# Modulo_control.net
KiCad netlist of a schematic drawn in Altium Designer
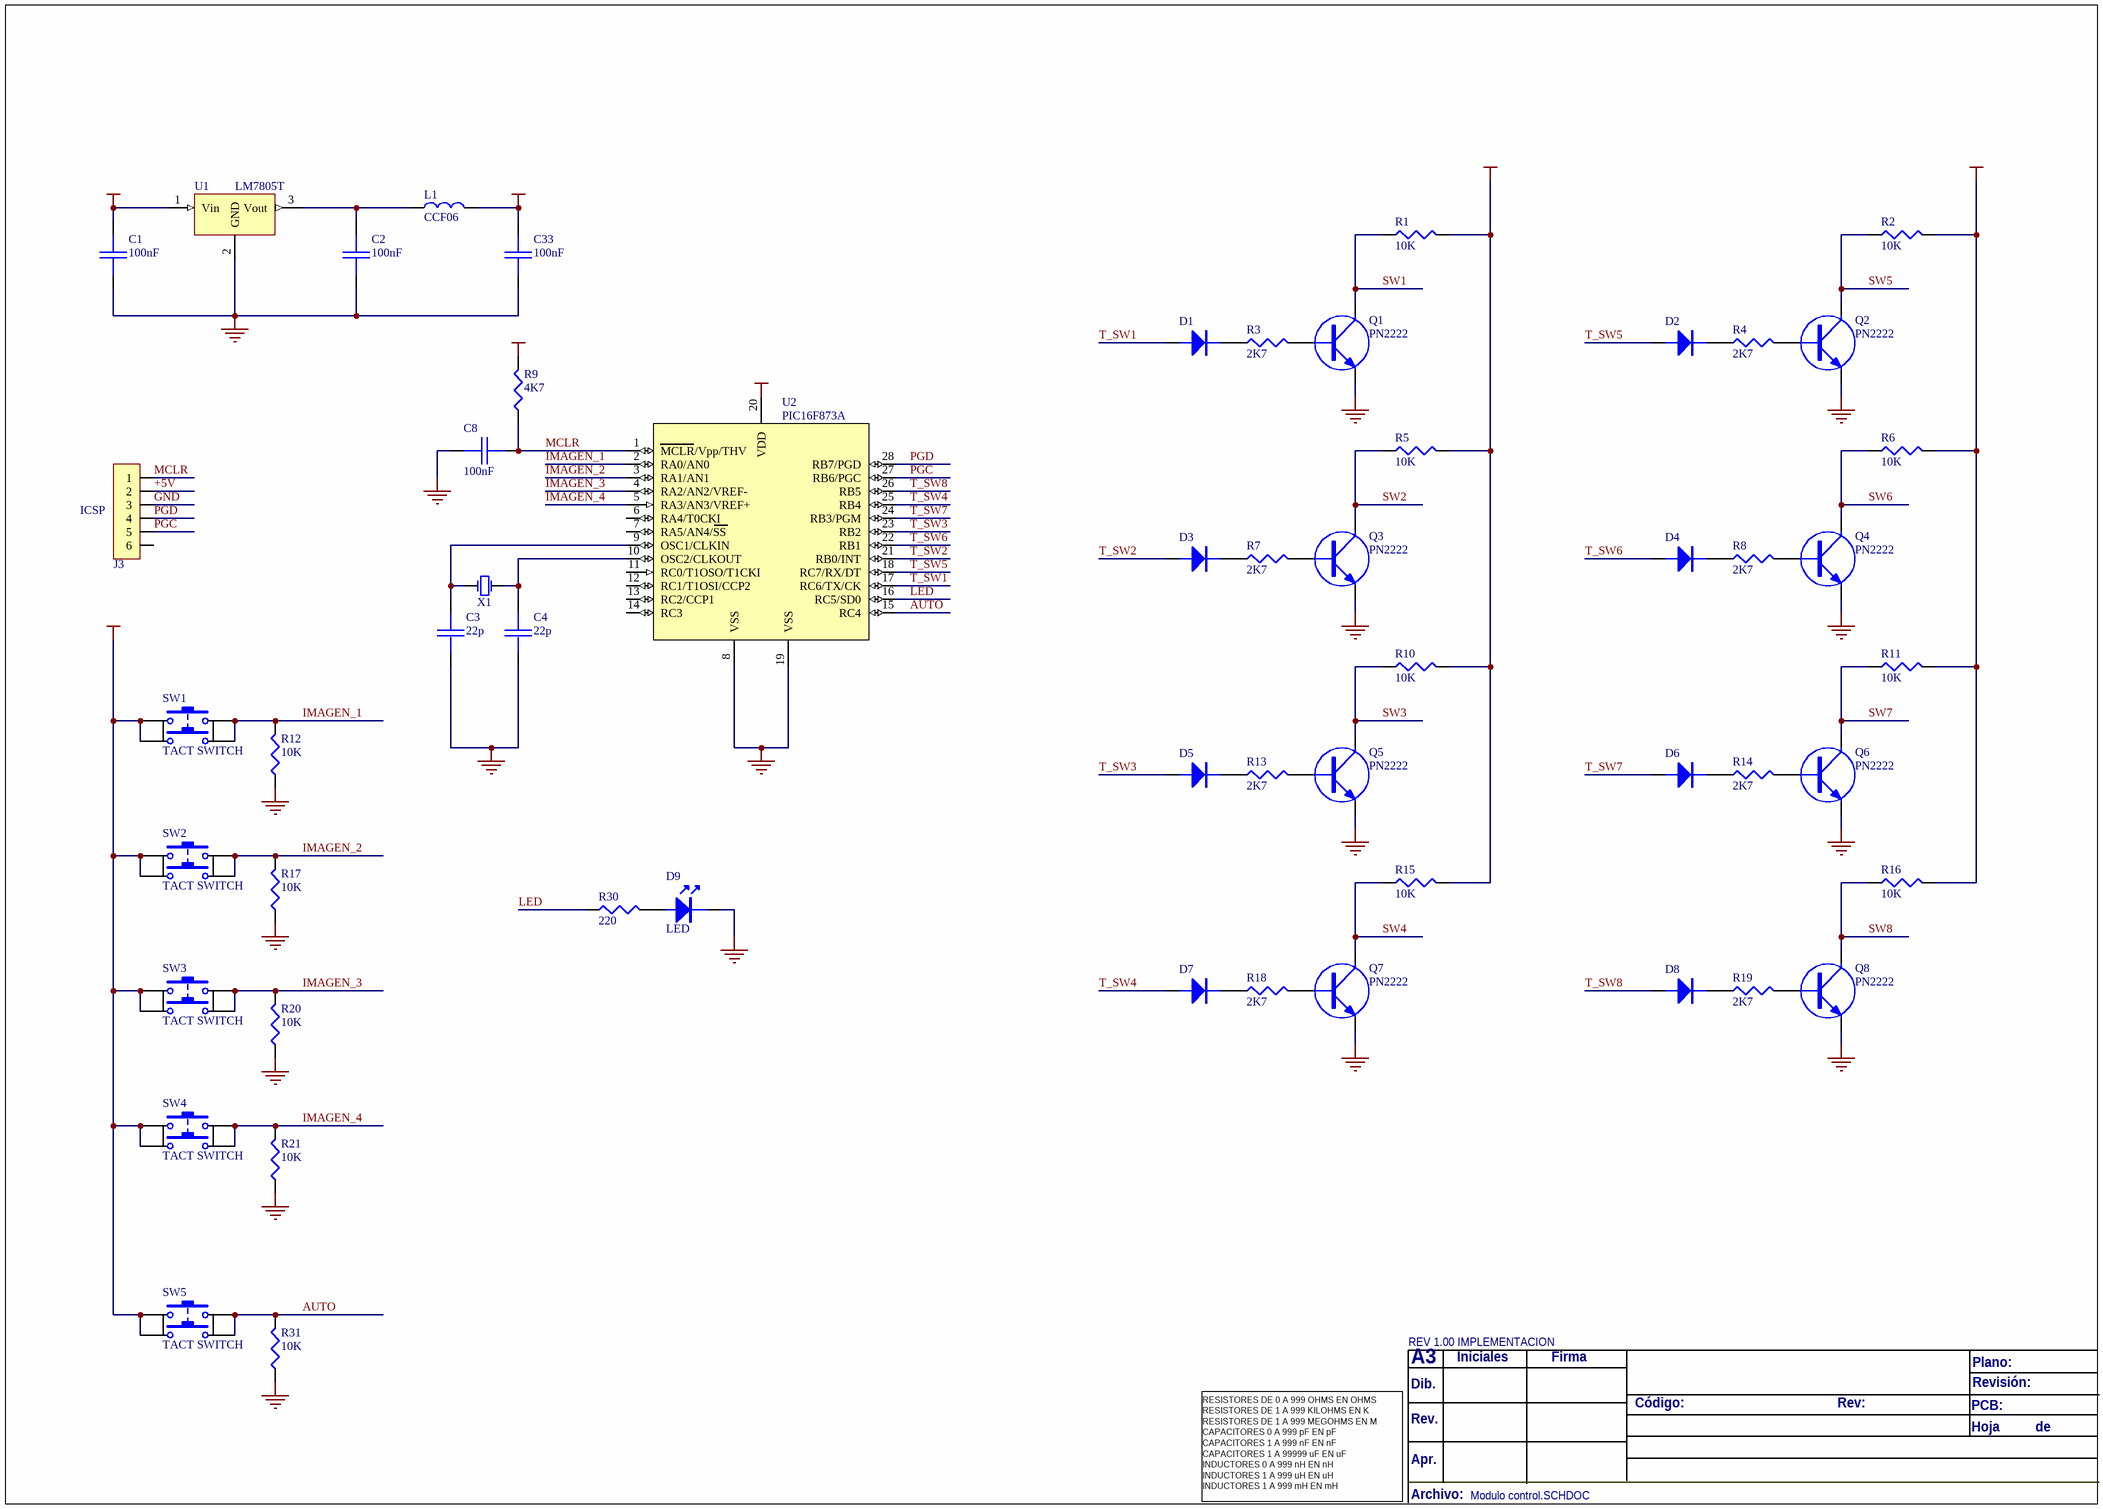
[diagram p0: Modulo control.SCHDOC]

(export (version "E")
  (design (tool "Eeschema 10.0.6"))
  (components
    (comp (ref "C1")
      (value "100nF")
      (footprint "0805")
      (description "CAPACITOR SMD 0805 X7R  50 V 100 nF")
      (libsource (lib "CAPACITORES SMD0805") (part "100n"))
    )
    (comp (ref "C2")
      (value "100nF")
      (footprint "0805")
      (description "CAPACITOR SMD 0805 X7R  50 V 100 nF")
      (libsource (lib "CAPACITORES SMD0805") (part "100n"))
    )
    (comp (ref "C3")
      (value "22p")
      (footprint "CAP5.08")
      (description "CAPACITOR PLATE NP0 100V PASO 2.54 mm 22 pF")
      (libsource (lib "CAPACITORES PLATE NP0") (part "22p"))
    )
    (comp (ref "C4")
      (value "22p")
      (footprint "CAP5.08")
      (description "CAPACITOR PLATE NP0 100V PASO 2.54 mm 22 pF")
      (libsource (lib "CAPACITORES PLATE NP0") (part "22p"))
    )
    (comp (ref "C8")
      (value "100nF")
      (footprint "0805")
      (description "CAPACITOR SMD 0805 X7R  50 V 100 nF")
      (libsource (lib "CAPACITORES SMD0805") (part "100n"))
    )
    (comp (ref "C33")
      (value "100nF")
      (footprint "0805")
      (description "CAPACITOR SMD 0805 X7R  50 V 100 nF")
      (libsource (lib "CAPACITORES SMD0805") (part "100n"))
    )
    (comp (ref "D1")
      (value "1N4148 DO-35")
      (footprint "DO-35_300")
      (description "1N4148 DO-35 DIODO")
      (libsource (lib "DIODOS") (part "1N4148 DO-35"))
    )
    (comp (ref "D2")
      (value "1N4148 DO-35")
      (footprint "DO-35_300")
      (description "1N4148 DO-35 DIODO")
      (libsource (lib "DIODOS") (part "1N4148 DO-35"))
    )
    (comp (ref "D3")
      (value "1N4148 DO-35")
      (footprint "DO-35_300")
      (description "1N4148 DO-35 DIODO")
      (libsource (lib "DIODOS") (part "1N4148 DO-35"))
    )
    (comp (ref "D4")
      (value "1N4148 DO-35")
      (footprint "DO-35_300")
      (description "1N4148 DO-35 DIODO")
      (libsource (lib "DIODOS") (part "1N4148 DO-35"))
    )
    (comp (ref "D5")
      (value "1N4148 DO-35")
      (footprint "DO-35_300")
      (description "1N4148 DO-35 DIODO")
      (libsource (lib "DIODOS") (part "1N4148 DO-35"))
    )
    (comp (ref "D6")
      (value "1N4148 DO-35")
      (footprint "DO-35_300")
      (description "1N4148 DO-35 DIODO")
      (libsource (lib "DIODOS") (part "1N4148 DO-35"))
    )
    (comp (ref "D7")
      (value "1N4148 DO-35")
      (footprint "DO-35_300")
      (description "1N4148 DO-35 DIODO")
      (libsource (lib "DIODOS") (part "1N4148 DO-35"))
    )
    (comp (ref "D8")
      (value "1N4148 DO-35")
      (footprint "DO-35_300")
      (description "1N4148 DO-35 DIODO")
      (libsource (lib "DIODOS") (part "1N4148 DO-35"))
    )
    (comp (ref "D9")
      (value "LED")
      (footprint "LED 3MM")
      (description "LED AMARILLO 3MM")
      (libsource (lib "DIODOS") (part "LED AMARILLO 3MM"))
    )
    (comp (ref "J3")
      (value "HEADER6")
      (footprint "JUMPER_6A")
      (description "TIRA MOLEX 1X6 11MM MACHO RECTA PARA PCB")
      (libsource (lib "CONECTORES") (part "HEADER6"))
    )
    (comp (ref "L1")
      (value "CCF06")
      (footprint "AXIAL10X4_300")
      (description "INDUCTOR CCF06")
      (libsource (lib "INDUCTORES") (part "CCF06"))
    )
    (comp (ref "Q1")
      (value "PN2222")
      (footprint "TO-92C")
      (description "PN2222 TO-92 NPN TRANSISTOR")
      (libsource (lib "TRANSISTORES") (part "PN2222"))
    )
    (comp (ref "Q2")
      (value "PN2222")
      (footprint "TO-92C")
      (description "PN2222 TO-92 NPN TRANSISTOR")
      (libsource (lib "TRANSISTORES") (part "PN2222"))
    )
    (comp (ref "Q3")
      (value "PN2222")
      (footprint "TO-92C")
      (description "PN2222 TO-92 NPN TRANSISTOR")
      (libsource (lib "TRANSISTORES") (part "PN2222"))
    )
    (comp (ref "Q4")
      (value "PN2222")
      (footprint "TO-92C")
      (description "PN2222 TO-92 NPN TRANSISTOR")
      (libsource (lib "TRANSISTORES") (part "PN2222"))
    )
    (comp (ref "Q5")
      (value "PN2222")
      (footprint "TO-92C")
      (description "PN2222 TO-92 NPN TRANSISTOR")
      (libsource (lib "TRANSISTORES") (part "PN2222"))
    )
    (comp (ref "Q6")
      (value "PN2222")
      (footprint "TO-92C")
      (description "PN2222 TO-92 NPN TRANSISTOR")
      (libsource (lib "TRANSISTORES") (part "PN2222"))
    )
    (comp (ref "Q7")
      (value "PN2222")
      (footprint "TO-92C")
      (description "PN2222 TO-92 NPN TRANSISTOR")
      (libsource (lib "TRANSISTORES") (part "PN2222"))
    )
    (comp (ref "Q8")
      (value "PN2222")
      (footprint "TO-92C")
      (description "PN2222 TO-92 NPN TRANSISTOR")
      (libsource (lib "TRANSISTORES") (part "PN2222"))
    )
    (comp (ref "R1")
      (value "10K")
      (footprint "RES_MF1/2W_200")
      (description "RESISTOR METAL FILM 0.5 W 5% 10 KILOHMS")
      (libsource (lib "RESISTORES METAL FILM MEDIO WATT") (part "10K"))
    )
    (comp (ref "R2")
      (value "10K")
      (footprint "RES_MF1/2W_200")
      (description "RESISTOR METAL FILM 0.5 W 5% 10 KILOHMS")
      (libsource (lib "RESISTORES METAL FILM MEDIO WATT") (part "10K"))
    )
    (comp (ref "R3")
      (value "2K7")
      (footprint "RES_MF1/2W_200")
      (description "RESISTOR METAL FILM 0.5 W 5% 2.7 KILOHMS")
      (libsource (lib "RESISTORES METAL FILM MEDIO WATT") (part "2K7"))
    )
    (comp (ref "R4")
      (value "2K7")
      (footprint "RES_MF1/2W_200")
      (description "RESISTOR METAL FILM 0.5 W 5% 2.7 KILOHMS")
      (libsource (lib "RESISTORES METAL FILM MEDIO WATT") (part "2K7"))
    )
    (comp (ref "R5")
      (value "10K")
      (footprint "RES_MF1/2W_200")
      (description "RESISTOR METAL FILM 0.5 W 5% 10 KILOHMS")
      (libsource (lib "RESISTORES METAL FILM MEDIO WATT") (part "10K"))
    )
    (comp (ref "R6")
      (value "10K")
      (footprint "RES_MF1/2W_200")
      (description "RESISTOR METAL FILM 0.5 W 5% 10 KILOHMS")
      (libsource (lib "RESISTORES METAL FILM MEDIO WATT") (part "10K"))
    )
    (comp (ref "R7")
      (value "2K7")
      (footprint "RES_MF1/2W_200")
      (description "RESISTOR METAL FILM 0.5 W 5% 2.7 KILOHMS")
      (libsource (lib "RESISTORES METAL FILM MEDIO WATT") (part "2K7"))
    )
    (comp (ref "R8")
      (value "2K7")
      (footprint "RES_MF1/2W_200")
      (description "RESISTOR METAL FILM 0.5 W 5% 2.7 KILOHMS")
      (libsource (lib "RESISTORES METAL FILM MEDIO WATT") (part "2K7"))
    )
    (comp (ref "R9")
      (value "4K7")
      (footprint "RES_MF1/2W_200")
      (description "RESISTOR METAL FILM 0.5 W 5% 4.7 KILOHMS")
      (libsource (lib "RESISTORES METAL FILM MEDIO WATT") (part "4K7"))
    )
    (comp (ref "R10")
      (value "10K")
      (footprint "RES_MF1/2W_200")
      (description "RESISTOR METAL FILM 0.5 W 5% 10 KILOHMS")
      (libsource (lib "RESISTORES METAL FILM MEDIO WATT") (part "10K"))
    )
    (comp (ref "R11")
      (value "10K")
      (footprint "RES_MF1/2W_200")
      (description "RESISTOR METAL FILM 0.5 W 5% 10 KILOHMS")
      (libsource (lib "RESISTORES METAL FILM MEDIO WATT") (part "10K"))
    )
    (comp (ref "R12")
      (value "10K")
      (footprint "RES_MF1/2W_200")
      (description "RESISTOR METAL FILM 0.5 W 5% 10 KILOHMS")
      (libsource (lib "RESISTORES METAL FILM MEDIO WATT") (part "10K"))
    )
    (comp (ref "R13")
      (value "2K7")
      (footprint "RES_MF1/2W_200")
      (description "RESISTOR METAL FILM 0.5 W 5% 2.7 KILOHMS")
      (libsource (lib "RESISTORES METAL FILM MEDIO WATT") (part "2K7"))
    )
    (comp (ref "R14")
      (value "2K7")
      (footprint "RES_MF1/2W_200")
      (description "RESISTOR METAL FILM 0.5 W 5% 2.7 KILOHMS")
      (libsource (lib "RESISTORES METAL FILM MEDIO WATT") (part "2K7"))
    )
    (comp (ref "R15")
      (value "10K")
      (footprint "RES_MF1/2W_200")
      (description "RESISTOR METAL FILM 0.5 W 5% 10 KILOHMS")
      (libsource (lib "RESISTORES METAL FILM MEDIO WATT") (part "10K"))
    )
    (comp (ref "R16")
      (value "10K")
      (footprint "RES_MF1/2W_200")
      (description "RESISTOR METAL FILM 0.5 W 5% 10 KILOHMS")
      (libsource (lib "RESISTORES METAL FILM MEDIO WATT") (part "10K"))
    )
    (comp (ref "R17")
      (value "10K")
      (footprint "RES_MF1/2W_200")
      (description "RESISTOR METAL FILM 0.5 W 5% 10 KILOHMS")
      (libsource (lib "RESISTORES METAL FILM MEDIO WATT") (part "10K"))
    )
    (comp (ref "R18")
      (value "2K7")
      (footprint "RES_MF1/2W_200")
      (description "RESISTOR METAL FILM 0.5 W 5% 2.7 KILOHMS")
      (libsource (lib "RESISTORES METAL FILM MEDIO WATT") (part "2K7"))
    )
    (comp (ref "R19")
      (value "2K7")
      (footprint "RES_MF1/2W_200")
      (description "RESISTOR METAL FILM 0.5 W 5% 2.7 KILOHMS")
      (libsource (lib "RESISTORES METAL FILM MEDIO WATT") (part "2K7"))
    )
    (comp (ref "R20")
      (value "10K")
      (footprint "RES_MF1/2W_200")
      (description "RESISTOR METAL FILM 0.5 W 5% 10 KILOHMS")
      (libsource (lib "RESISTORES METAL FILM MEDIO WATT") (part "10K"))
    )
    (comp (ref "R21")
      (value "10K")
      (footprint "RES_MF1/2W_200")
      (description "RESISTOR METAL FILM 0.5 W 5% 10 KILOHMS")
      (libsource (lib "RESISTORES METAL FILM MEDIO WATT") (part "10K"))
    )
    (comp (ref "R30")
      (value "220")
      (footprint "0805")
      (description "RESISTOR SMD0805 0.125 W 5%  220 OHMS")
      (libsource (lib "RESISTORES SMD0805") (part "220"))
    )
    (comp (ref "R31")
      (value "10K")
      (footprint "RES_MF1/2W_200")
      (description "RESISTOR METAL FILM 0.5 W 5% 10 KILOHMS")
      (libsource (lib "RESISTORES METAL FILM MEDIO WATT") (part "10K"))
    )
    (comp (ref "SW1")
      (value "TACT SWITCH")
      (footprint "PULSADOR 6X6")
      (description "TACT SWITCH 6X6X12MM 4PINES TSWTS065")
      (libsource (lib "LLAVES") (part "SW-PB"))
    )
    (comp (ref "SW2")
      (value "TACT SWITCH")
      (footprint "PULSADOR 6X6")
      (description "TACT SWITCH 6X6X12MM 4PINES TSWTS065")
      (libsource (lib "LLAVES") (part "SW-PB"))
    )
    (comp (ref "SW3")
      (value "TACT SWITCH")
      (footprint "PULSADOR 6X6")
      (description "TACT SWITCH 6X6X12MM 4PINES TSWTS065")
      (libsource (lib "LLAVES") (part "SW-PB"))
    )
    (comp (ref "SW4")
      (value "TACT SWITCH")
      (footprint "PULSADOR 6X6")
      (description "TACT SWITCH 6X6X12MM 4PINES TSWTS065")
      (libsource (lib "LLAVES") (part "SW-PB"))
    )
    (comp (ref "SW5")
      (value "TACT SWITCH")
      (footprint "PULSADOR 6X6")
      (description "TACT SWITCH 6X6X12MM 4PINES TSWTS065")
      (libsource (lib "LLAVES") (part "SW-PB"))
    )
    (comp (ref "U1")
      (value "LM7805T")
      (footprint "TO-220_1")
      (description "LM7805T TO-220 CIRC INT")
      (libsource (lib "CIRCUITOS INTEGRADOS DIP") (part "LM7805T"))
    )
    (comp (ref "U2")
      (value "PIC16F873A")
      (footprint "DIP28F")
      (description "PIC-16F873A - I/SP DIP28 7.62 MM")
      (libsource (lib "CIRCUITOS INTEGRADOS DIP") (part "PIC-16F873A"))
    )
    (comp (ref "X1")
      (value "XL20M-UM5")
      (footprint "UM5")
      (description "XL20M-UM5 CRISTAL DE 20 MHZ 10ppm")
      (libsource (lib "CRISTALES") (part "XL20M-UM5"))
    )
  )
  (nets
    (net (code "1") (name "+5V") (class "Default")
      (node (ref "C33") (pin "1") (pintype "passive"))
      (node (ref "J3") (pin "2") (pinfunction "2_2") (pintype "passive"))
      (node (ref "L1") (pin "2") (pintype "passive"))
      (node (ref "R9") (pin "2") (pintype "passive"))
      (node (ref "SW1") (pin "1") (pinfunction "1_1") (pintype "passive"))
      (node (ref "SW1") (pin "3") (pinfunction "3_3") (pintype "passive"))
      (node (ref "SW2") (pin "1") (pinfunction "1_1") (pintype "passive"))
      (node (ref "SW2") (pin "3") (pinfunction "3_3") (pintype "passive"))
      (node (ref "SW3") (pin "1") (pinfunction "1_1") (pintype "passive"))
      (node (ref "SW3") (pin "3") (pinfunction "3_3") (pintype "passive"))
      (node (ref "SW4") (pin "1") (pinfunction "1_1") (pintype "passive"))
      (node (ref "SW4") (pin "3") (pinfunction "3_3") (pintype "passive"))
      (node (ref "SW5") (pin "1") (pinfunction "1_1") (pintype "passive"))
      (node (ref "SW5") (pin "3") (pinfunction "3_3") (pintype "passive"))
      (node (ref "U2") (pin "20") (pinfunction "VDD_20") (pintype "power_in"))
    )
    (net (code "2") (name "/AUTO") (class "Default")
      (node (ref "R31") (pin "2") (pintype "passive"))
      (node (ref "SW5") (pin "2") (pinfunction "2_2") (pintype "passive"))
      (node (ref "SW5") (pin "4") (pinfunction "4_4") (pintype "passive"))
      (node (ref "U2") (pin "15") (pinfunction "RC4_15") (pintype "bidirectional"))
    )
    (net (code "3") (name "/IMAGEN_1") (class "Default")
      (node (ref "R12") (pin "2") (pintype "passive"))
      (node (ref "SW1") (pin "2") (pinfunction "2_2") (pintype "passive"))
      (node (ref "SW1") (pin "4") (pinfunction "4_4") (pintype "passive"))
      (node (ref "U2") (pin "2") (pinfunction "RA0/AN0_2") (pintype "bidirectional"))
    )
    (net (code "4") (name "/IMAGEN_2") (class "Default")
      (node (ref "R17") (pin "2") (pintype "passive"))
      (node (ref "SW2") (pin "2") (pinfunction "2_2") (pintype "passive"))
      (node (ref "SW2") (pin "4") (pinfunction "4_4") (pintype "passive"))
      (node (ref "U2") (pin "3") (pinfunction "RA1/AN1_3") (pintype "bidirectional"))
    )
    (net (code "5") (name "/IMAGEN_3") (class "Default")
      (node (ref "R20") (pin "2") (pintype "passive"))
      (node (ref "SW3") (pin "2") (pinfunction "2_2") (pintype "passive"))
      (node (ref "SW3") (pin "4") (pinfunction "4_4") (pintype "passive"))
      (node (ref "U2") (pin "4") (pinfunction "RA2/AN2/VREF-_4") (pintype "bidirectional"))
    )
    (net (code "6") (name "/IMAGEN_4") (class "Default")
      (node (ref "R21") (pin "2") (pintype "passive"))
      (node (ref "SW4") (pin "2") (pinfunction "2_2") (pintype "passive"))
      (node (ref "SW4") (pin "4") (pinfunction "4_4") (pintype "passive"))
      (node (ref "U2") (pin "5") (pinfunction "RA3/AN3/VREF+_5") (pintype "input"))
    )
    (net (code "7") (name "/LED") (class "Default")
      (node (ref "R30") (pin "1") (pintype "passive"))
      (node (ref "U2") (pin "16") (pinfunction "RC5/SD0_16") (pintype "bidirectional"))
    )
    (net (code "8") (name "/MCLR") (class "Default")
      (node (ref "C8") (pin "2") (pintype "passive"))
      (node (ref "J3") (pin "1") (pinfunction "1_1") (pintype "passive"))
      (node (ref "R9") (pin "1") (pintype "passive"))
      (node (ref "U2") (pin "1") (pinfunction "MCLR/Vpp/THV_1") (pintype "bidirectional"))
    )
    (net (code "9") (name "/PGC") (class "Default")
      (node (ref "J3") (pin "5") (pinfunction "5_5") (pintype "passive"))
      (node (ref "U2") (pin "27") (pinfunction "RB6/PGC_27") (pintype "bidirectional"))
    )
    (net (code "10") (name "/PGD") (class "Default")
      (node (ref "J3") (pin "4") (pinfunction "4_4") (pintype "passive"))
      (node (ref "U2") (pin "28") (pinfunction "RB7/PGD_28") (pintype "bidirectional"))
    )
    (net (code "11") (name "/SW1") (class "Default")
      (node (ref "Q1") (pin "3") (pinfunction "C_3") (pintype "passive"))
      (node (ref "R1") (pin "1") (pintype "passive"))
    )
    (net (code "12") (name "/SW2") (class "Default")
      (node (ref "Q3") (pin "3") (pinfunction "C_3") (pintype "passive"))
      (node (ref "R5") (pin "1") (pintype "passive"))
    )
    (net (code "13") (name "/SW3") (class "Default")
      (node (ref "Q5") (pin "3") (pinfunction "C_3") (pintype "passive"))
      (node (ref "R10") (pin "1") (pintype "passive"))
    )
    (net (code "14") (name "/SW4") (class "Default")
      (node (ref "Q7") (pin "3") (pinfunction "C_3") (pintype "passive"))
      (node (ref "R15") (pin "1") (pintype "passive"))
    )
    (net (code "15") (name "/SW5") (class "Default")
      (node (ref "Q2") (pin "3") (pinfunction "C_3") (pintype "passive"))
      (node (ref "R2") (pin "1") (pintype "passive"))
    )
    (net (code "16") (name "/SW6") (class "Default")
      (node (ref "Q4") (pin "3") (pinfunction "C_3") (pintype "passive"))
      (node (ref "R6") (pin "1") (pintype "passive"))
    )
    (net (code "17") (name "/SW7") (class "Default")
      (node (ref "Q6") (pin "3") (pinfunction "C_3") (pintype "passive"))
      (node (ref "R11") (pin "1") (pintype "passive"))
    )
    (net (code "18") (name "/SW8") (class "Default")
      (node (ref "Q8") (pin "3") (pinfunction "C_3") (pintype "passive"))
      (node (ref "R16") (pin "1") (pintype "passive"))
    )
    (net (code "19") (name "/T_SW1") (class "Default")
      (node (ref "D1") (pin "A") (pinfunction "A_A") (pintype "passive"))
      (node (ref "U2") (pin "17") (pinfunction "RC6/TX/CK_17") (pintype "bidirectional"))
    )
    (net (code "20") (name "/T_SW2") (class "Default")
      (node (ref "D3") (pin "A") (pinfunction "A_A") (pintype "passive"))
      (node (ref "U2") (pin "21") (pinfunction "RB0/INT_21") (pintype "bidirectional"))
    )
    (net (code "21") (name "/T_SW3") (class "Default")
      (node (ref "D5") (pin "A") (pinfunction "A_A") (pintype "passive"))
      (node (ref "U2") (pin "23") (pinfunction "RB2_23") (pintype "bidirectional"))
    )
    (net (code "22") (name "/T_SW4") (class "Default")
      (node (ref "D7") (pin "A") (pinfunction "A_A") (pintype "passive"))
      (node (ref "U2") (pin "25") (pinfunction "RB4_25") (pintype "bidirectional"))
    )
    (net (code "23") (name "/T_SW5") (class "Default")
      (node (ref "D2") (pin "A") (pinfunction "A_A") (pintype "passive"))
      (node (ref "U2") (pin "18") (pinfunction "RC7/RX/DT_18") (pintype "bidirectional"))
    )
    (net (code "24") (name "/T_SW6") (class "Default")
      (node (ref "D4") (pin "A") (pinfunction "A_A") (pintype "passive"))
      (node (ref "U2") (pin "22") (pinfunction "RB1_22") (pintype "bidirectional"))
    )
    (net (code "25") (name "/T_SW7") (class "Default")
      (node (ref "D6") (pin "A") (pinfunction "A_A") (pintype "passive"))
      (node (ref "U2") (pin "24") (pinfunction "RB3/PGM_24") (pintype "bidirectional"))
    )
    (net (code "26") (name "/T_SW8") (class "Default")
      (node (ref "D8") (pin "A") (pinfunction "A_A") (pintype "passive"))
      (node (ref "U2") (pin "26") (pinfunction "RB5_26") (pintype "bidirectional"))
    )
    (net (code "27") (name "GND") (class "Default")
      (node (ref "C1") (pin "2") (pintype "passive"))
      (node (ref "C2") (pin "2") (pintype "passive"))
      (node (ref "C3") (pin "1") (pintype "passive"))
      (node (ref "C33") (pin "2") (pintype "passive"))
      (node (ref "C4") (pin "1") (pintype "passive"))
      (node (ref "C8") (pin "1") (pintype "passive"))
      (node (ref "D9") (pin "K") (pinfunction "K_K") (pintype "passive"))
      (node (ref "J3") (pin "3") (pinfunction "3_3") (pintype "passive"))
      (node (ref "Q1") (pin "1") (pinfunction "E_1") (pintype "passive"))
      (node (ref "Q2") (pin "1") (pinfunction "E_1") (pintype "passive"))
      (node (ref "Q3") (pin "1") (pinfunction "E_1") (pintype "passive"))
      (node (ref "Q4") (pin "1") (pinfunction "E_1") (pintype "passive"))
      (node (ref "Q5") (pin "1") (pinfunction "E_1") (pintype "passive"))
      (node (ref "Q6") (pin "1") (pinfunction "E_1") (pintype "passive"))
      (node (ref "Q7") (pin "1") (pinfunction "E_1") (pintype "passive"))
      (node (ref "Q8") (pin "1") (pinfunction "E_1") (pintype "passive"))
      (node (ref "R12") (pin "1") (pintype "passive"))
      (node (ref "R17") (pin "1") (pintype "passive"))
      (node (ref "R20") (pin "1") (pintype "passive"))
      (node (ref "R21") (pin "1") (pintype "passive"))
      (node (ref "R31") (pin "1") (pintype "passive"))
      (node (ref "U1") (pin "2") (pinfunction "GND_2") (pintype "passive"))
      (node (ref "U2") (pin "19") (pinfunction "VSS_19") (pintype "passive"))
      (node (ref "U2") (pin "8") (pinfunction "VSS_8") (pintype "passive"))
    )
    (net (code "28") (name "Net-(D1-PadK)") (class "Default")
      (node (ref "D1") (pin "K") (pinfunction "K_K") (pintype "passive"))
      (node (ref "R3") (pin "1") (pintype "passive"))
    )
    (net (code "29") (name "Net-(D2-PadK)") (class "Default")
      (node (ref "D2") (pin "K") (pinfunction "K_K") (pintype "passive"))
      (node (ref "R4") (pin "1") (pintype "passive"))
    )
    (net (code "30") (name "Net-(D3-PadK)") (class "Default")
      (node (ref "D3") (pin "K") (pinfunction "K_K") (pintype "passive"))
      (node (ref "R7") (pin "1") (pintype "passive"))
    )
    (net (code "31") (name "Net-(D4-PadK)") (class "Default")
      (node (ref "D4") (pin "K") (pinfunction "K_K") (pintype "passive"))
      (node (ref "R8") (pin "1") (pintype "passive"))
    )
    (net (code "32") (name "Net-(D5-PadK)") (class "Default")
      (node (ref "D5") (pin "K") (pinfunction "K_K") (pintype "passive"))
      (node (ref "R13") (pin "1") (pintype "passive"))
    )
    (net (code "33") (name "Net-(D6-PadK)") (class "Default")
      (node (ref "D6") (pin "K") (pinfunction "K_K") (pintype "passive"))
      (node (ref "R14") (pin "1") (pintype "passive"))
    )
    (net (code "34") (name "Net-(D7-PadK)") (class "Default")
      (node (ref "D7") (pin "K") (pinfunction "K_K") (pintype "passive"))
      (node (ref "R18") (pin "1") (pintype "passive"))
    )
    (net (code "35") (name "Net-(D8-PadK)") (class "Default")
      (node (ref "D8") (pin "K") (pinfunction "K_K") (pintype "passive"))
      (node (ref "R19") (pin "1") (pintype "passive"))
    )
    (net (code "36") (name "Net-(D9-PadA)") (class "Default")
      (node (ref "D9") (pin "A") (pinfunction "A_A") (pintype "passive"))
      (node (ref "R30") (pin "2") (pintype "passive"))
    )
    (net (code "37") (name "Net-(Q1-B)") (class "Default")
      (node (ref "Q1") (pin "2") (pinfunction "B_2") (pintype "passive"))
      (node (ref "R3") (pin "2") (pintype "passive"))
    )
    (net (code "38") (name "Net-(Q2-B)") (class "Default")
      (node (ref "Q2") (pin "2") (pinfunction "B_2") (pintype "passive"))
      (node (ref "R4") (pin "2") (pintype "passive"))
    )
    (net (code "39") (name "Net-(Q3-B)") (class "Default")
      (node (ref "Q3") (pin "2") (pinfunction "B_2") (pintype "passive"))
      (node (ref "R7") (pin "2") (pintype "passive"))
    )
    (net (code "40") (name "Net-(Q4-B)") (class "Default")
      (node (ref "Q4") (pin "2") (pinfunction "B_2") (pintype "passive"))
      (node (ref "R8") (pin "2") (pintype "passive"))
    )
    (net (code "41") (name "Net-(Q5-B)") (class "Default")
      (node (ref "Q5") (pin "2") (pinfunction "B_2") (pintype "passive"))
      (node (ref "R13") (pin "2") (pintype "passive"))
    )
    (net (code "42") (name "Net-(Q6-B)") (class "Default")
      (node (ref "Q6") (pin "2") (pinfunction "B_2") (pintype "passive"))
      (node (ref "R14") (pin "2") (pintype "passive"))
    )
    (net (code "43") (name "Net-(Q7-B)") (class "Default")
      (node (ref "Q7") (pin "2") (pinfunction "B_2") (pintype "passive"))
      (node (ref "R18") (pin "2") (pintype "passive"))
    )
    (net (code "44") (name "Net-(Q8-B)") (class "Default")
      (node (ref "Q8") (pin "2") (pinfunction "B_2") (pintype "passive"))
      (node (ref "R19") (pin "2") (pintype "passive"))
    )
    (net (code "45") (name "Net-(U1-Vout)") (class "Default")
      (node (ref "C2") (pin "1") (pintype "passive"))
      (node (ref "L1") (pin "1") (pintype "passive"))
      (node (ref "U1") (pin "3") (pinfunction "Vout_3") (pintype "output"))
    )
    (net (code "46") (name "Net-(U2-OSC1{slash}CLKIN)") (class "Default")
      (node (ref "C3") (pin "2") (pintype "passive"))
      (node (ref "U2") (pin "9") (pinfunction "OSC1/CLKIN_9") (pintype "bidirectional"))
      (node (ref "X1") (pin "2") (pinfunction "OSC2_2") (pintype "passive"))
    )
    (net (code "47") (name "Net-(U2-OSC2{slash}CLKOUT)") (class "Default")
      (node (ref "C4") (pin "2") (pintype "passive"))
      (node (ref "U2") (pin "10") (pinfunction "OSC2/CLKOUT_10") (pintype "bidirectional"))
      (node (ref "X1") (pin "1") (pinfunction "OSC1_1") (pintype "passive"))
    )
    (net (code "48") (name "VCC") (class "Default")
      (node (ref "C1") (pin "1") (pintype "passive"))
      (node (ref "R1") (pin "2") (pintype "passive"))
      (node (ref "R10") (pin "2") (pintype "passive"))
      (node (ref "R11") (pin "2") (pintype "passive"))
      (node (ref "R15") (pin "2") (pintype "passive"))
      (node (ref "R16") (pin "2") (pintype "passive"))
      (node (ref "R2") (pin "2") (pintype "passive"))
      (node (ref "R5") (pin "2") (pintype "passive"))
      (node (ref "R6") (pin "2") (pintype "passive"))
      (node (ref "U1") (pin "1") (pinfunction "Vin_1") (pintype "input"))
    )
    (net (code "49") (name "unconnected-(J3-Pad6)") (class "Default")
      (node (ref "J3") (pin "6") (pinfunction "6_6") (pintype "passive"))
    )
    (net (code "50") (name "unconnected-(U2-RA4{slash}T0CKI-Pad6)") (class "Default")
      (node (ref "U2") (pin "6") (pinfunction "RA4/T0CKI_6") (pintype "bidirectional"))
    )
    (net (code "51") (name "unconnected-(U2-RA5{slash}AN4{slash}SS-Pad7)") (class "Default")
      (node (ref "U2") (pin "7") (pinfunction "RA5/AN4/SS_7") (pintype "bidirectional"))
    )
    (net (code "52") (name "unconnected-(U2-RC0{slash}T1OSO{slash}T1CKI-Pad11)") (class "Default")
      (node (ref "U2") (pin "11") (pinfunction "RC0/T1OSO/T1CKI_11") (pintype "input"))
    )
    (net (code "53") (name "unconnected-(U2-RC1{slash}T1OSI{slash}CCP2-Pad12)") (class "Default")
      (node (ref "U2") (pin "12") (pinfunction "RC1/T1OSI/CCP2_12") (pintype "bidirectional"))
    )
    (net (code "54") (name "unconnected-(U2-RC2{slash}CCP1-Pad13)") (class "Default")
      (node (ref "U2") (pin "13") (pinfunction "RC2/CCP1_13") (pintype "bidirectional"))
    )
    (net (code "55") (name "unconnected-(U2-RC3-Pad14)") (class "Default")
      (node (ref "U2") (pin "14") (pinfunction "RC3_14") (pintype "bidirectional"))
    )
  )
)
